# ACtoDc.net
KiCad netlist of a schematic drawn in Altium Designer
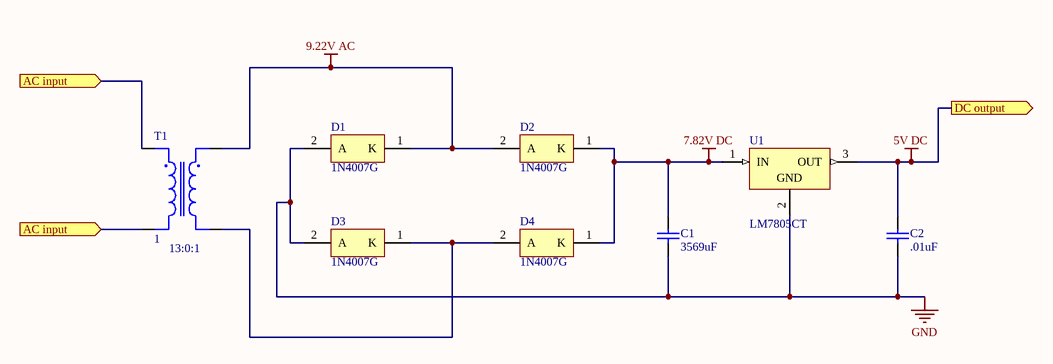
[diagram p0: ACtoDc.SchDoc]

(export (version "E")
  (design (tool "Eeschema 10.0.6"))
  (components
    (comp (ref "C1")
      (value "3569uF")
      (description "Capacitor")
      (libsource (lib "Simulation Generic Components") (part "Capacitor"))
    )
    (comp (ref "C2")
      (value ".01uF")
      (description "Capacitor")
      (libsource (lib "Simulation Generic Components") (part "Capacitor"))
    )
    (comp (ref "D1")
      (value "1N4007G")
      (footprint "ONSC-AXIAL_LEAD-2-59-10_P")
      (description "Standard Recovery Rectifier, 2-Pin Axial_Lead, Pb-Free, Bulk Bag")
      (fields (field (name "MANUFACTURER") "On Semiconductor"))
      (libsource (lib "Altium Content Vault") (part "ONSC-D-K1A2-2_A"))
    )
    (comp (ref "D2")
      (value "1N4007G")
      (footprint "ONSC-AXIAL_LEAD-2-59-10_P")
      (description "Standard Recovery Rectifier, 2-Pin Axial_Lead, Pb-Free, Bulk Bag")
      (fields (field (name "MANUFACTURER") "On Semiconductor"))
      (libsource (lib "Altium Content Vault") (part "ONSC-D-K1A2-2_A"))
    )
    (comp (ref "D3")
      (value "1N4007G")
      (footprint "ONSC-AXIAL_LEAD-2-59-10_P")
      (description "Standard Recovery Rectifier, 2-Pin Axial_Lead, Pb-Free, Bulk Bag")
      (fields (field (name "MANUFACTURER") "On Semiconductor"))
      (libsource (lib "Altium Content Vault") (part "ONSC-D-K1A2-2_A"))
    )
    (comp (ref "D4")
      (value "1N4007G")
      (footprint "ONSC-AXIAL_LEAD-2-59-10_P")
      (description "Standard Recovery Rectifier, 2-Pin Axial_Lead, Pb-Free, Bulk Bag")
      (fields (field (name "MANUFACTURER") "On Semiconductor"))
      (libsource (lib "Altium Content Vault") (part "ONSC-D-K1A2-2_A"))
    )
    (comp (ref "T1")
      (value "Ideal Transformer")
      (fields (field (name "GAIN") "1"))
      (libsource (lib "Simulation Generic Components") (part "Transformer Ideal"))
    )
    (comp (ref "U1")
      (value "LM7805CT")
      (footprint "FAIR-TO-220-3")
      (description "Positive Voltage Regulator, 5 V, 1 A, -40 to 125 degC, 3-Pin TO-220, RoHS, Tube")
      (fields (field (name "MANUFACTURER") "FairchildSemiconductor"))
      (libsource (lib "Altium Content Vault") (part "FAIR-LM7805CT-TO220-3"))
    )
  )
  (nets
    (net (code "1") (name "/AC input") (class "Default")
      (node (ref "T1") (pin "1") (pinfunction "1_1") (pintype "passive"))
      (node (ref "T1") (pin "2") (pinfunction "2_2") (pintype "passive"))
    )
    (net (code "2") (name "5V DC") (class "Default")
      (node (ref "C2") (pin "2") (pinfunction "2_2") (pintype "passive"))
      (node (ref "U1") (pin "3") (pinfunction "OUT_3") (pintype "output"))
    )
    (net (code "3") (name "7.82V DC") (class "Default")
      (node (ref "C1") (pin "2") (pinfunction "2_2") (pintype "passive"))
      (node (ref "D2") (pin "1") (pinfunction "K_1") (pintype "passive"))
      (node (ref "D4") (pin "1") (pinfunction "K_1") (pintype "passive"))
      (node (ref "U1") (pin "1") (pinfunction "IN_1") (pintype "input"))
    )
    (net (code "4") (name "9.22V AC") (class "Default")
      (node (ref "D1") (pin "1") (pinfunction "K_1") (pintype "passive"))
      (node (ref "D2") (pin "2") (pinfunction "A_2") (pintype "passive"))
      (node (ref "T1") (pin "3") (pinfunction "3_3") (pintype "passive"))
    )
    (net (code "5") (name "GND") (class "Default")
      (node (ref "C1") (pin "1") (pinfunction "1_1") (pintype "passive"))
      (node (ref "C2") (pin "1") (pinfunction "1_1") (pintype "passive"))
      (node (ref "D1") (pin "2") (pinfunction "A_2") (pintype "passive"))
      (node (ref "D3") (pin "2") (pinfunction "A_2") (pintype "passive"))
      (node (ref "U1") (pin "2") (pinfunction "GND_2") (pintype "power_in"))
    )
    (net (code "6") (name "Net-(D3-K)") (class "Default")
      (node (ref "D3") (pin "1") (pinfunction "K_1") (pintype "passive"))
      (node (ref "D4") (pin "2") (pinfunction "A_2") (pintype "passive"))
      (node (ref "T1") (pin "4") (pinfunction "4_4") (pintype "passive"))
    )
  )
)
